# xwoofer.net
KiCad netlist of a schematic drawn in EAGLE
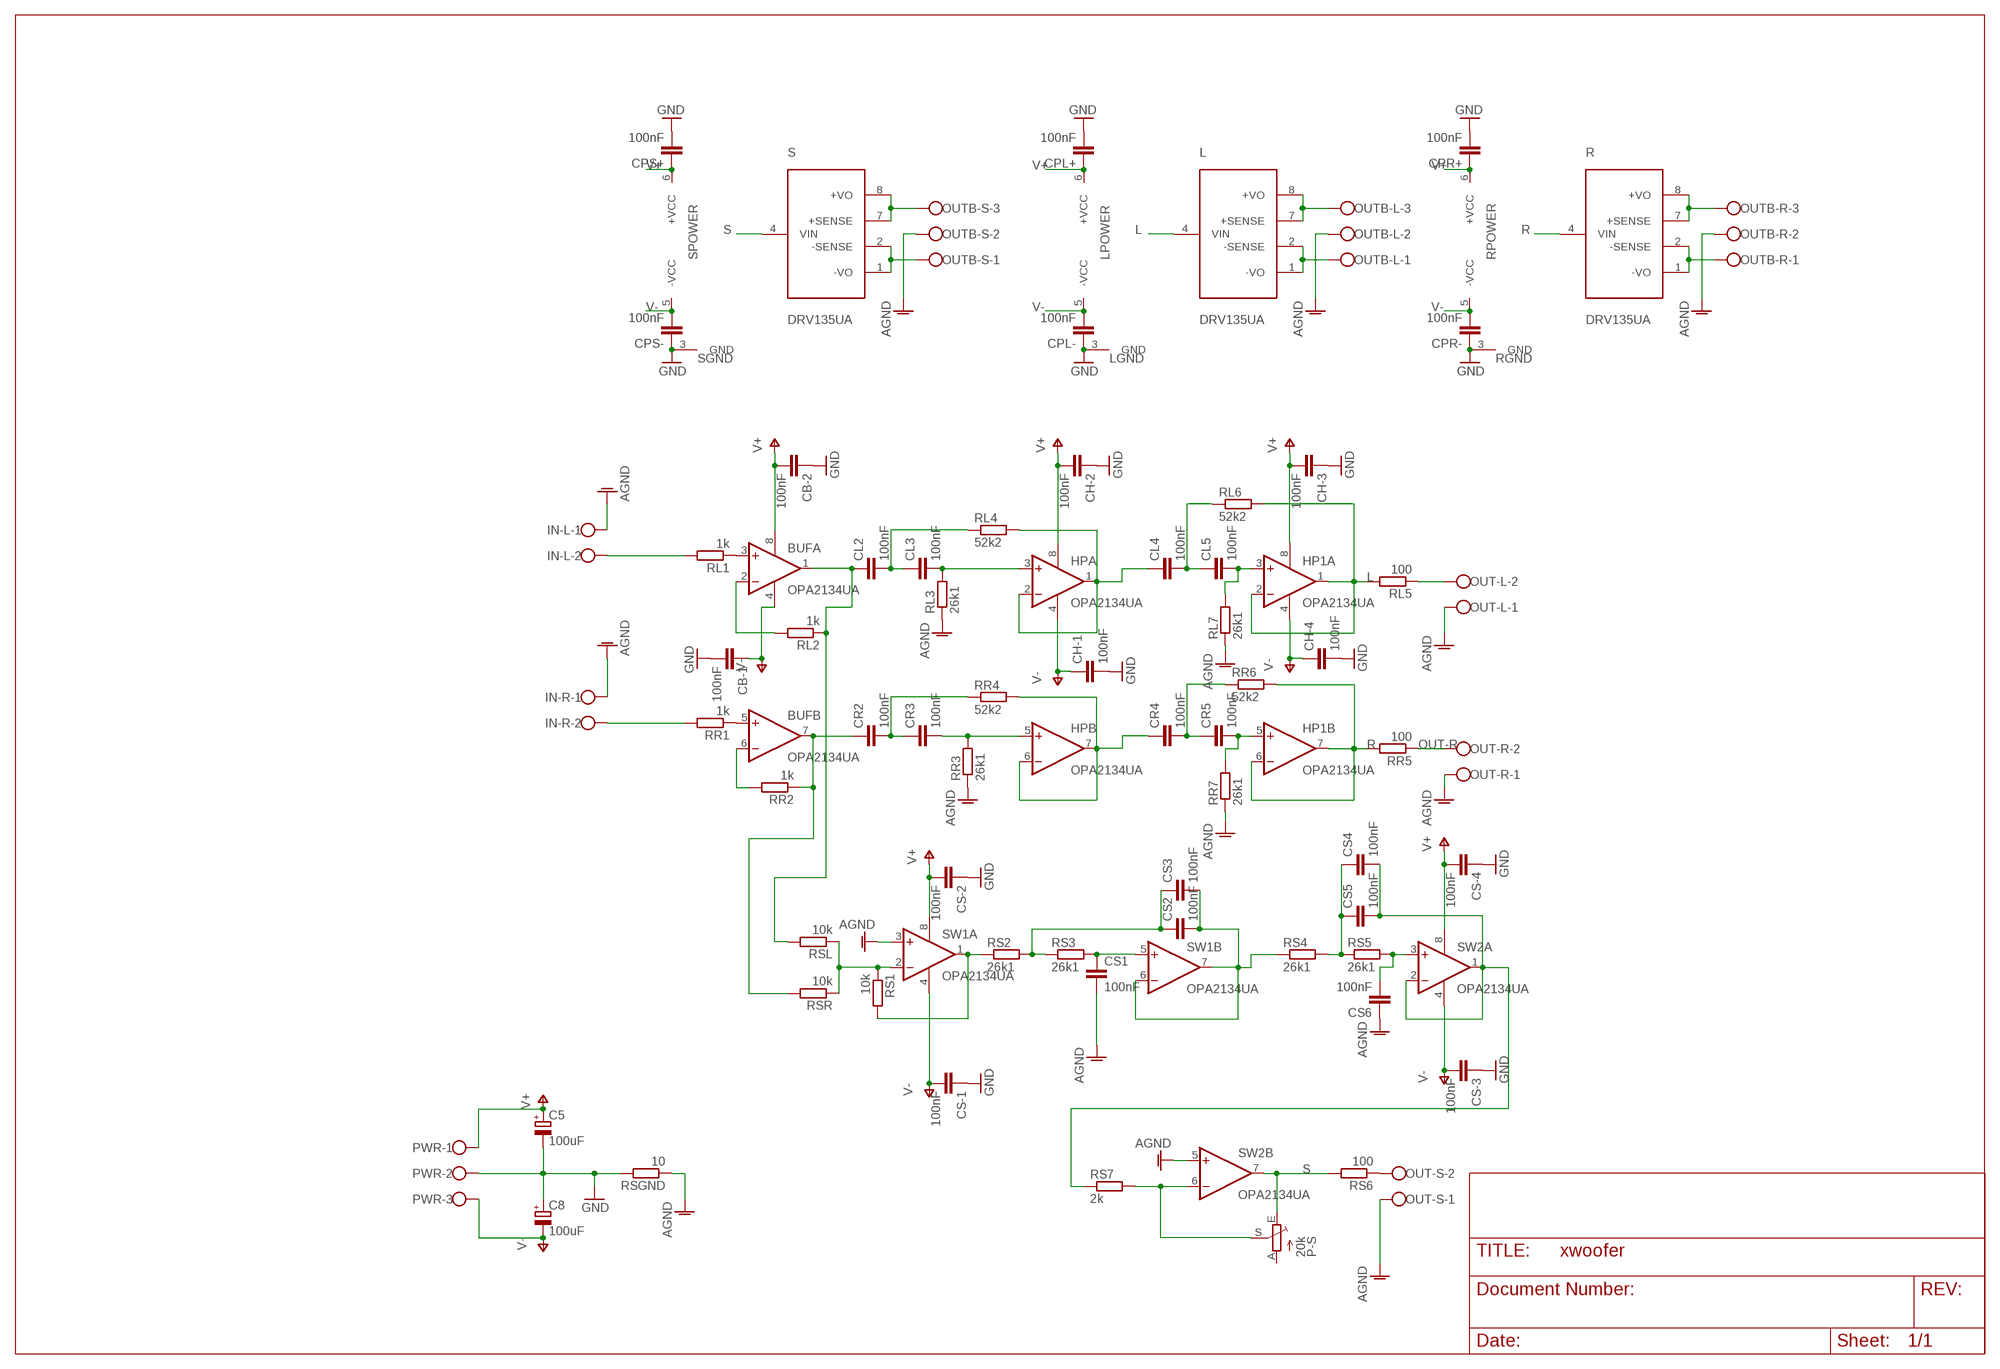
[diagram p0: schematic, sheet 1]

(export (version "E")
  (design (tool "Eeschema 10.0.6"))
  (components
    (comp (ref "BUF")
      (value "OPA2134UA")
      (footprint "eagle-import:SO08")
      (libsource (lib "eagle-import") (part "OPA2UA134"))
    )
    (comp (ref "C5")
      (value "100uF")
      (footprint "eagle-import:E2,5-7")
      (libsource (lib "eagle-import") (part "CPOL-EUE2.5-7"))
    )
    (comp (ref "C8")
      (value "100uF")
      (footprint "eagle-import:E2,5-7")
      (libsource (lib "eagle-import") (part "CPOL-EUE2.5-7"))
    )
    (comp (ref "CB-1")
      (value "100nF")
      (footprint "eagle-import:C0805")
      (libsource (lib "eagle-import") (part "C-EUC0805"))
    )
    (comp (ref "CB-2")
      (value "100nF")
      (footprint "eagle-import:C0805")
      (libsource (lib "eagle-import") (part "C-EUC0805"))
    )
    (comp (ref "CH-1")
      (value "100nF")
      (footprint "eagle-import:C0805K")
      (libsource (lib "eagle-import") (part "C-EUC0805K"))
    )
    (comp (ref "CH-2")
      (value "100nF")
      (footprint "eagle-import:C0805K")
      (libsource (lib "eagle-import") (part "C-EUC0805K"))
    )
    (comp (ref "CH-3")
      (value "100nF")
      (footprint "eagle-import:C0805K")
      (libsource (lib "eagle-import") (part "C-EUC0805K"))
    )
    (comp (ref "CH-4")
      (value "100nF")
      (footprint "eagle-import:C0805K")
      (libsource (lib "eagle-import") (part "C-EUC0805K"))
    )
    (comp (ref "CL2")
      (value "100nF")
      (footprint "eagle-import:C025-025X050")
      (libsource (lib "eagle-import") (part "C-EU025-025X050"))
    )
    (comp (ref "CL3")
      (value "100nF")
      (footprint "eagle-import:C025-025X050")
      (libsource (lib "eagle-import") (part "C-EU025-025X050"))
    )
    (comp (ref "CL4")
      (value "100nF")
      (footprint "eagle-import:C025-025X050")
      (libsource (lib "eagle-import") (part "C-EU025-025X050"))
    )
    (comp (ref "CL5")
      (value "100nF")
      (footprint "eagle-import:C025-025X050")
      (libsource (lib "eagle-import") (part "C-EU025-025X050"))
    )
    (comp (ref "CPL+")
      (value "100nF")
      (footprint "eagle-import:C0805K")
      (libsource (lib "eagle-import") (part "C-EUC0805K"))
    )
    (comp (ref "CPL-")
      (value "100nF")
      (footprint "eagle-import:C0805K")
      (libsource (lib "eagle-import") (part "C-EUC0805K"))
    )
    (comp (ref "CPR+")
      (value "100nF")
      (footprint "eagle-import:C0805K")
      (libsource (lib "eagle-import") (part "C-EUC0805K"))
    )
    (comp (ref "CPR-")
      (value "100nF")
      (footprint "eagle-import:C0805K")
      (libsource (lib "eagle-import") (part "C-EUC0805K"))
    )
    (comp (ref "CPS+")
      (value "100nF")
      (footprint "eagle-import:C0805K")
      (libsource (lib "eagle-import") (part "C-EUC0805K"))
    )
    (comp (ref "CPS-")
      (value "100nF")
      (footprint "eagle-import:C0805K")
      (libsource (lib "eagle-import") (part "C-EUC0805K"))
    )
    (comp (ref "CR2")
      (value "100nF")
      (footprint "eagle-import:C025-025X050")
      (libsource (lib "eagle-import") (part "C-EU025-025X050"))
    )
    (comp (ref "CR3")
      (value "100nF")
      (footprint "eagle-import:C025-025X050")
      (libsource (lib "eagle-import") (part "C-EU025-025X050"))
    )
    (comp (ref "CR4")
      (value "100nF")
      (footprint "eagle-import:C025-025X050")
      (libsource (lib "eagle-import") (part "C-EU025-025X050"))
    )
    (comp (ref "CR5")
      (value "100nF")
      (footprint "eagle-import:C025-025X050")
      (libsource (lib "eagle-import") (part "C-EU025-025X050"))
    )
    (comp (ref "CS-1")
      (value "100nF")
      (footprint "eagle-import:C0805K")
      (libsource (lib "eagle-import") (part "C-EUC0805K"))
    )
    (comp (ref "CS-2")
      (value "100nF")
      (footprint "eagle-import:C0805K")
      (libsource (lib "eagle-import") (part "C-EUC0805K"))
    )
    (comp (ref "CS-3")
      (value "100nF")
      (footprint "eagle-import:C0805K")
      (libsource (lib "eagle-import") (part "C-EUC0805K"))
    )
    (comp (ref "CS-4")
      (value "100nF")
      (footprint "eagle-import:C0805K")
      (libsource (lib "eagle-import") (part "C-EUC0805K"))
    )
    (comp (ref "CS1")
      (value "100nF")
      (footprint "eagle-import:C025-025X050")
      (libsource (lib "eagle-import") (part "C-EU025-025X050"))
    )
    (comp (ref "CS2")
      (value "100nF")
      (footprint "eagle-import:C025-025X050")
      (libsource (lib "eagle-import") (part "C-EU025-025X050"))
    )
    (comp (ref "CS3")
      (value "100nF")
      (footprint "eagle-import:C025-025X050")
      (libsource (lib "eagle-import") (part "C-EU025-025X050"))
    )
    (comp (ref "CS4")
      (value "100nF")
      (footprint "eagle-import:C025-025X050")
      (libsource (lib "eagle-import") (part "C-EU025-025X050"))
    )
    (comp (ref "CS5")
      (value "100nF")
      (footprint "eagle-import:C025-025X050")
      (libsource (lib "eagle-import") (part "C-EU025-025X050"))
    )
    (comp (ref "CS6")
      (value "100nF")
      (footprint "eagle-import:C025-025X050")
      (libsource (lib "eagle-import") (part "C-EU025-025X050"))
    )
    (comp (ref "HP")
      (value "OPA2134UA")
      (footprint "eagle-import:SO08")
      (libsource (lib "eagle-import") (part "OPA2UA134"))
    )
    (comp (ref "HP1")
      (value "OPA2134UA")
      (footprint "eagle-import:SO08")
      (libsource (lib "eagle-import") (part "OPA2UA134"))
    )
    (comp (ref "IN-L")
      (value "W237-102")
      (footprint "eagle-import:W237-102")
      (libsource (lib "eagle-import") (part "W237-102"))
    )
    (comp (ref "IN-R")
      (value "W237-102")
      (footprint "eagle-import:W237-102")
      (libsource (lib "eagle-import") (part "W237-102"))
    )
    (comp (ref "L")
      (value "DRV135UA")
      (footprint "eagle-import:SO08")
      (libsource (lib "eagle-import") (part "DRV135UA"))
    )
    (comp (ref "OUT-L")
      (value "W237-102")
      (footprint "eagle-import:W237-102")
      (libsource (lib "eagle-import") (part "W237-102"))
    )
    (comp (ref "OUT-R")
      (value "W237-102")
      (footprint "eagle-import:W237-102")
      (libsource (lib "eagle-import") (part "W237-102"))
    )
    (comp (ref "OUT-S")
      (value "W237-102")
      (footprint "eagle-import:W237-102")
      (libsource (lib "eagle-import") (part "W237-102"))
    )
    (comp (ref "OUTB-L")
      (value "W237-103")
      (footprint "eagle-import:W237-103")
      (fields (field (name "MPN") "237-103"))
      (libsource (lib "eagle-import") (part "W237-103"))
    )
    (comp (ref "OUTB-R")
      (value "W237-103")
      (footprint "eagle-import:W237-103")
      (fields (field (name "MPN") "237-103"))
      (libsource (lib "eagle-import") (part "W237-103"))
    )
    (comp (ref "OUTB-S")
      (value "W237-103")
      (footprint "eagle-import:W237-103")
      (fields (field (name "MPN") "237-103"))
      (libsource (lib "eagle-import") (part "W237-103"))
    )
    (comp (ref "P-S")
      (value "20k")
      (footprint "eagle-import:B64Y")
      (libsource (lib "eagle-import") (part "TRIM_EU-B64Y"))
    )
    (comp (ref "PWR")
      (value "W237-103")
      (footprint "eagle-import:W237-103")
      (fields (field (name "MPN") "237-103"))
      (libsource (lib "eagle-import") (part "W237-103"))
    )
    (comp (ref "R")
      (value "DRV135UA")
      (footprint "eagle-import:SO08")
      (libsource (lib "eagle-import") (part "DRV135UA"))
    )
    (comp (ref "RL1")
      (value "1k")
      (footprint "eagle-import:R0603")
      (libsource (lib "eagle-import") (part "R-EU_R0603"))
    )
    (comp (ref "RL2")
      (value "1k")
      (footprint "eagle-import:R0603")
      (libsource (lib "eagle-import") (part "R-EU_R0603"))
    )
    (comp (ref "RL3")
      (value "26k1")
      (footprint "eagle-import:R0603")
      (libsource (lib "eagle-import") (part "R-EU_R0603"))
    )
    (comp (ref "RL4")
      (value "52k2")
      (footprint "eagle-import:R0603")
      (libsource (lib "eagle-import") (part "R-EU_R0603"))
    )
    (comp (ref "RL5")
      (value "100")
      (footprint "eagle-import:R1206")
      (libsource (lib "eagle-import") (part "R-EU_R1206"))
    )
    (comp (ref "RL6")
      (value "52k2")
      (footprint "eagle-import:R0603")
      (libsource (lib "eagle-import") (part "R-EU_R0603"))
    )
    (comp (ref "RL7")
      (value "26k1")
      (footprint "eagle-import:R0603")
      (libsource (lib "eagle-import") (part "R-EU_R0603"))
    )
    (comp (ref "RR1")
      (value "1k")
      (footprint "eagle-import:R0603")
      (libsource (lib "eagle-import") (part "R-EU_R0603"))
    )
    (comp (ref "RR2")
      (value "1k")
      (footprint "eagle-import:R0603")
      (libsource (lib "eagle-import") (part "R-EU_R0603"))
    )
    (comp (ref "RR3")
      (value "26k1")
      (footprint "eagle-import:R0603")
      (libsource (lib "eagle-import") (part "R-EU_R0603"))
    )
    (comp (ref "RR4")
      (value "52k2")
      (footprint "eagle-import:R0603")
      (libsource (lib "eagle-import") (part "R-EU_R0603"))
    )
    (comp (ref "RR5")
      (value "100")
      (footprint "eagle-import:R1206")
      (libsource (lib "eagle-import") (part "R-EU_R1206"))
    )
    (comp (ref "RR6")
      (value "52k2")
      (footprint "eagle-import:R0603")
      (libsource (lib "eagle-import") (part "R-EU_R0603"))
    )
    (comp (ref "RR7")
      (value "26k1")
      (footprint "eagle-import:R0603")
      (libsource (lib "eagle-import") (part "R-EU_R0603"))
    )
    (comp (ref "RS1")
      (value "10k")
      (footprint "eagle-import:R0603")
      (libsource (lib "eagle-import") (part "R-EU_R0603"))
    )
    (comp (ref "RS2")
      (value "26k1")
      (footprint "eagle-import:R0603")
      (libsource (lib "eagle-import") (part "R-EU_R0603"))
    )
    (comp (ref "RS3")
      (value "26k1")
      (footprint "eagle-import:R0603")
      (libsource (lib "eagle-import") (part "R-EU_R0603"))
    )
    (comp (ref "RS4")
      (value "26k1")
      (footprint "eagle-import:R0603")
      (libsource (lib "eagle-import") (part "R-EU_R0603"))
    )
    (comp (ref "RS5")
      (value "26k1")
      (footprint "eagle-import:R0603")
      (libsource (lib "eagle-import") (part "R-EU_R0603"))
    )
    (comp (ref "RS6")
      (value "100")
      (footprint "eagle-import:R1206")
      (libsource (lib "eagle-import") (part "R-EU_R1206"))
    )
    (comp (ref "RS7")
      (value "2k")
      (footprint "eagle-import:R0603")
      (libsource (lib "eagle-import") (part "R-EU_R0603"))
    )
    (comp (ref "RSGND")
      (value "10")
      (footprint "eagle-import:R1206")
      (libsource (lib "eagle-import") (part "R-EU_R1206"))
    )
    (comp (ref "RSL")
      (value "10k")
      (footprint "eagle-import:R0603")
      (libsource (lib "eagle-import") (part "R-EU_R0603"))
    )
    (comp (ref "RSR")
      (value "10k")
      (footprint "eagle-import:R0603")
      (libsource (lib "eagle-import") (part "R-EU_R0603"))
    )
    (comp (ref "S")
      (value "DRV135UA")
      (footprint "eagle-import:SO08")
      (libsource (lib "eagle-import") (part "DRV135UA"))
    )
    (comp (ref "SW1")
      (value "OPA2134UA")
      (footprint "eagle-import:SO08")
      (libsource (lib "eagle-import") (part "OPA2UA134"))
    )
    (comp (ref "SW2")
      (value "OPA2134UA")
      (footprint "eagle-import:SO08")
      (libsource (lib "eagle-import") (part "OPA2UA134"))
    )
  )
  (nets
    (net (code "1") (name "/L") (class "Default")
      (node (ref "HP1") (pin "1") (pinfunction "OUT_1") (pintype "output"))
      (node (ref "HP1") (pin "2") (pinfunction "-IN_2") (pintype "input"))
      (node (ref "L") (pin "4") (pinfunction "VIN_4") (pintype "bidirectional"))
      (node (ref "RL5") (pin "2") (pinfunction "2_2") (pintype "passive"))
      (node (ref "RL6") (pin "2") (pinfunction "2_2") (pintype "passive"))
    )
    (net (code "2") (name "/OUT-R") (class "Default")
      (node (ref "OUT-R") (pin "2") (pinfunction "KL_2") (pintype "passive"))
      (node (ref "RR5") (pin "1") (pinfunction "1_1") (pintype "passive"))
    )
    (net (code "3") (name "/R") (class "Default")
      (node (ref "HP1") (pin "6") (pinfunction "-IN_6") (pintype "input"))
      (node (ref "HP1") (pin "7") (pinfunction "OUT_7") (pintype "output"))
      (node (ref "R") (pin "4") (pinfunction "VIN_4") (pintype "bidirectional"))
      (node (ref "RR5") (pin "2") (pinfunction "2_2") (pintype "passive"))
      (node (ref "RR6") (pin "2") (pinfunction "2_2") (pintype "passive"))
    )
    (net (code "4") (name "/S") (class "Default")
      (node (ref "P-S") (pin "E") (pinfunction "E_E") (pintype "passive"))
      (node (ref "RS6") (pin "2") (pinfunction "2_2") (pintype "passive"))
      (node (ref "S") (pin "4") (pinfunction "VIN_4") (pintype "bidirectional"))
      (node (ref "SW2") (pin "7") (pinfunction "OUT_7") (pintype "output"))
    )
    (net (code "5") (name "AGND") (class "Default")
      (node (ref "CS1") (pin "2") (pinfunction "2_2") (pintype "passive"))
      (node (ref "CS6") (pin "1") (pinfunction "1_1") (pintype "passive"))
      (node (ref "IN-L") (pin "1") (pinfunction "KL_1") (pintype "passive"))
      (node (ref "IN-R") (pin "1") (pinfunction "KL_1") (pintype "passive"))
      (node (ref "OUT-L") (pin "1") (pinfunction "KL_1") (pintype "passive"))
      (node (ref "OUT-R") (pin "1") (pinfunction "KL_1") (pintype "passive"))
      (node (ref "OUT-S") (pin "1") (pinfunction "KL_1") (pintype "passive"))
      (node (ref "OUTB-L") (pin "2") (pinfunction "KL_2") (pintype "passive"))
      (node (ref "OUTB-R") (pin "2") (pinfunction "KL_2") (pintype "passive"))
      (node (ref "OUTB-S") (pin "2") (pinfunction "KL_2") (pintype "passive"))
      (node (ref "RL3") (pin "1") (pinfunction "1_1") (pintype "passive"))
      (node (ref "RL7") (pin "1") (pinfunction "1_1") (pintype "passive"))
      (node (ref "RR3") (pin "1") (pinfunction "1_1") (pintype "passive"))
      (node (ref "RR7") (pin "1") (pinfunction "1_1") (pintype "passive"))
      (node (ref "RSGND") (pin "1") (pinfunction "1_1") (pintype "passive"))
      (node (ref "SW1") (pin "3") (pinfunction "+IN_3") (pintype "input"))
      (node (ref "SW2") (pin "5") (pinfunction "+IN_5") (pintype "input"))
    )
    (net (code "6") (name "GND") (class "Default")
      (node (ref "C5") (pin "-") (pinfunction "-_-") (pintype "passive"))
      (node (ref "C8") (pin "+") (pinfunction "+_+") (pintype "passive"))
      (node (ref "CB-1") (pin "2") (pinfunction "2_2") (pintype "passive"))
      (node (ref "CB-2") (pin "1") (pinfunction "1_1") (pintype "passive"))
      (node (ref "CH-1") (pin "2") (pinfunction "2_2") (pintype "passive"))
      (node (ref "CH-2") (pin "1") (pinfunction "1_1") (pintype "passive"))
      (node (ref "CH-3") (pin "1") (pinfunction "1_1") (pintype "passive"))
      (node (ref "CH-4") (pin "2") (pinfunction "2_2") (pintype "passive"))
      (node (ref "CPL+") (pin "2") (pinfunction "2_2") (pintype "passive"))
      (node (ref "CPL-") (pin "1") (pinfunction "1_1") (pintype "passive"))
      (node (ref "CPR+") (pin "2") (pinfunction "2_2") (pintype "passive"))
      (node (ref "CPR-") (pin "1") (pinfunction "1_1") (pintype "passive"))
      (node (ref "CPS+") (pin "2") (pinfunction "2_2") (pintype "passive"))
      (node (ref "CPS-") (pin "1") (pinfunction "1_1") (pintype "passive"))
      (node (ref "CS-1") (pin "1") (pinfunction "1_1") (pintype "passive"))
      (node (ref "CS-2") (pin "1") (pinfunction "1_1") (pintype "passive"))
      (node (ref "CS-3") (pin "1") (pinfunction "1_1") (pintype "passive"))
      (node (ref "CS-4") (pin "1") (pinfunction "1_1") (pintype "passive"))
      (node (ref "L") (pin "3") (pinfunction "GND_3") (pintype "power_in"))
      (node (ref "PWR") (pin "2") (pinfunction "KL_2") (pintype "passive"))
      (node (ref "R") (pin "3") (pinfunction "GND_3") (pintype "power_in"))
      (node (ref "RSGND") (pin "2") (pinfunction "2_2") (pintype "passive"))
      (node (ref "S") (pin "3") (pinfunction "GND_3") (pintype "power_in"))
    )
    (net (code "7") (name "Net-(BUFA-+IN)") (class "Default")
      (node (ref "BUF") (pin "3") (pinfunction "+IN_3") (pintype "input"))
      (node (ref "RL1") (pin "1") (pinfunction "1_1") (pintype "passive"))
    )
    (net (code "8") (name "Net-(BUFA--IN)") (class "Default")
      (node (ref "BUF") (pin "2") (pinfunction "-IN_2") (pintype "input"))
      (node (ref "RL2") (pin "2") (pinfunction "2_2") (pintype "passive"))
    )
    (net (code "9") (name "Net-(BUFA-OUT)") (class "Default")
      (node (ref "BUF") (pin "1") (pinfunction "OUT_1") (pintype "output"))
      (node (ref "CL2") (pin "1") (pinfunction "1_1") (pintype "passive"))
      (node (ref "RL2") (pin "1") (pinfunction "1_1") (pintype "passive"))
      (node (ref "RSL") (pin "2") (pinfunction "2_2") (pintype "passive"))
    )
    (net (code "10") (name "Net-(BUFB-+IN)") (class "Default")
      (node (ref "BUF") (pin "5") (pinfunction "+IN_5") (pintype "input"))
      (node (ref "RR1") (pin "1") (pinfunction "1_1") (pintype "passive"))
    )
    (net (code "11") (name "Net-(BUFB--IN)") (class "Default")
      (node (ref "BUF") (pin "6") (pinfunction "-IN_6") (pintype "input"))
      (node (ref "RR2") (pin "2") (pinfunction "2_2") (pintype "passive"))
    )
    (net (code "12") (name "Net-(BUFB-OUT)") (class "Default")
      (node (ref "BUF") (pin "7") (pinfunction "OUT_7") (pintype "output"))
      (node (ref "CR2") (pin "1") (pinfunction "1_1") (pintype "passive"))
      (node (ref "RR2") (pin "1") (pinfunction "1_1") (pintype "passive"))
      (node (ref "RSR") (pin "2") (pinfunction "2_2") (pintype "passive"))
    )
    (net (code "13") (name "Net-(CL2-Pad2)") (class "Default")
      (node (ref "CL2") (pin "2") (pinfunction "2_2") (pintype "passive"))
      (node (ref "CL3") (pin "1") (pinfunction "1_1") (pintype "passive"))
      (node (ref "RL4") (pin "1") (pinfunction "1_1") (pintype "passive"))
    )
    (net (code "14") (name "Net-(CL4-Pad2)") (class "Default")
      (node (ref "CL4") (pin "2") (pinfunction "2_2") (pintype "passive"))
      (node (ref "CL5") (pin "1") (pinfunction "1_1") (pintype "passive"))
      (node (ref "RL6") (pin "1") (pinfunction "1_1") (pintype "passive"))
    )
    (net (code "15") (name "Net-(CR2-Pad2)") (class "Default")
      (node (ref "CR2") (pin "2") (pinfunction "2_2") (pintype "passive"))
      (node (ref "CR3") (pin "1") (pinfunction "1_1") (pintype "passive"))
      (node (ref "RR4") (pin "1") (pinfunction "1_1") (pintype "passive"))
    )
    (net (code "16") (name "Net-(CR4-Pad2)") (class "Default")
      (node (ref "CR4") (pin "2") (pinfunction "2_2") (pintype "passive"))
      (node (ref "CR5") (pin "1") (pinfunction "1_1") (pintype "passive"))
      (node (ref "RR6") (pin "1") (pinfunction "1_1") (pintype "passive"))
    )
    (net (code "17") (name "Net-(CS2-Pad1)") (class "Default")
      (node (ref "CS2") (pin "1") (pinfunction "1_1") (pintype "passive"))
      (node (ref "CS3") (pin "1") (pinfunction "1_1") (pintype "passive"))
      (node (ref "RS2") (pin "2") (pinfunction "2_2") (pintype "passive"))
      (node (ref "RS3") (pin "1") (pinfunction "1_1") (pintype "passive"))
    )
    (net (code "18") (name "Net-(CS4-Pad1)") (class "Default")
      (node (ref "CS4") (pin "1") (pinfunction "1_1") (pintype "passive"))
      (node (ref "CS5") (pin "1") (pinfunction "1_1") (pintype "passive"))
      (node (ref "RS4") (pin "2") (pinfunction "2_2") (pintype "passive"))
      (node (ref "RS5") (pin "1") (pinfunction "1_1") (pintype "passive"))
    )
    (net (code "19") (name "Net-(HP1A-+IN)") (class "Default")
      (node (ref "CL5") (pin "2") (pinfunction "2_2") (pintype "passive"))
      (node (ref "HP1") (pin "3") (pinfunction "+IN_3") (pintype "input"))
      (node (ref "RL7") (pin "2") (pinfunction "2_2") (pintype "passive"))
    )
    (net (code "20") (name "Net-(HP1B-+IN)") (class "Default")
      (node (ref "CR5") (pin "2") (pinfunction "2_2") (pintype "passive"))
      (node (ref "HP1") (pin "5") (pinfunction "+IN_5") (pintype "input"))
      (node (ref "RR7") (pin "2") (pinfunction "2_2") (pintype "passive"))
    )
    (net (code "21") (name "Net-(HPA-+IN)") (class "Default")
      (node (ref "CL3") (pin "2") (pinfunction "2_2") (pintype "passive"))
      (node (ref "HP") (pin "3") (pinfunction "+IN_3") (pintype "input"))
      (node (ref "RL3") (pin "2") (pinfunction "2_2") (pintype "passive"))
    )
    (net (code "22") (name "Net-(HPA--IN)") (class "Default")
      (node (ref "CL4") (pin "1") (pinfunction "1_1") (pintype "passive"))
      (node (ref "HP") (pin "1") (pinfunction "OUT_1") (pintype "output"))
      (node (ref "HP") (pin "2") (pinfunction "-IN_2") (pintype "input"))
      (node (ref "RL4") (pin "2") (pinfunction "2_2") (pintype "passive"))
    )
    (net (code "23") (name "Net-(HPB-+IN)") (class "Default")
      (node (ref "CR3") (pin "2") (pinfunction "2_2") (pintype "passive"))
      (node (ref "HP") (pin "5") (pinfunction "+IN_5") (pintype "input"))
      (node (ref "RR3") (pin "2") (pinfunction "2_2") (pintype "passive"))
    )
    (net (code "24") (name "Net-(HPB--IN)") (class "Default")
      (node (ref "CR4") (pin "1") (pinfunction "1_1") (pintype "passive"))
      (node (ref "HP") (pin "6") (pinfunction "-IN_6") (pintype "input"))
      (node (ref "HP") (pin "7") (pinfunction "OUT_7") (pintype "output"))
      (node (ref "RR4") (pin "2") (pinfunction "2_2") (pintype "passive"))
    )
    (net (code "25") (name "Net-(IN-LB-KL)") (class "Default")
      (node (ref "IN-L") (pin "2") (pinfunction "KL_2") (pintype "passive"))
      (node (ref "RL1") (pin "2") (pinfunction "2_2") (pintype "passive"))
    )
    (net (code "26") (name "Net-(IN-RB-KL)") (class "Default")
      (node (ref "IN-R") (pin "2") (pinfunction "KL_2") (pintype "passive"))
      (node (ref "RR1") (pin "2") (pinfunction "2_2") (pintype "passive"))
    )
    (net (code "27") (name "Net-(LA-+SENSE)") (class "Default")
      (node (ref "L") (pin "7") (pinfunction "+SENSE_7") (pintype "bidirectional"))
      (node (ref "L") (pin "8") (pinfunction "+VO_8") (pintype "bidirectional"))
      (node (ref "OUTB-L") (pin "3") (pinfunction "KL_3") (pintype "passive"))
    )
    (net (code "28") (name "Net-(LA--SENSE)") (class "Default")
      (node (ref "L") (pin "1") (pinfunction "-VO_1") (pintype "bidirectional"))
      (node (ref "L") (pin "2") (pinfunction "-SENSE_2") (pintype "bidirectional"))
      (node (ref "OUTB-L") (pin "1") (pinfunction "KL_1") (pintype "passive"))
    )
    (net (code "29") (name "Net-(OUT-LB-KL)") (class "Default")
      (node (ref "OUT-L") (pin "2") (pinfunction "KL_2") (pintype "passive"))
      (node (ref "RL5") (pin "1") (pinfunction "1_1") (pintype "passive"))
    )
    (net (code "30") (name "Net-(OUT-SB-KL)") (class "Default")
      (node (ref "OUT-S") (pin "2") (pinfunction "KL_2") (pintype "passive"))
      (node (ref "RS6") (pin "1") (pinfunction "1_1") (pintype "passive"))
    )
    (net (code "31") (name "Net-(OUTB-RA-KL)") (class "Default")
      (node (ref "OUTB-R") (pin "1") (pinfunction "KL_1") (pintype "passive"))
      (node (ref "R") (pin "1") (pinfunction "-VO_1") (pintype "bidirectional"))
      (node (ref "R") (pin "2") (pinfunction "-SENSE_2") (pintype "bidirectional"))
    )
    (net (code "32") (name "Net-(OUTB-RC-KL)") (class "Default")
      (node (ref "OUTB-R") (pin "3") (pinfunction "KL_3") (pintype "passive"))
      (node (ref "R") (pin "7") (pinfunction "+SENSE_7") (pintype "bidirectional"))
      (node (ref "R") (pin "8") (pinfunction "+VO_8") (pintype "bidirectional"))
    )
    (net (code "33") (name "Net-(OUTB-SA-KL)") (class "Default")
      (node (ref "OUTB-S") (pin "1") (pinfunction "KL_1") (pintype "passive"))
      (node (ref "S") (pin "1") (pinfunction "-VO_1") (pintype "bidirectional"))
      (node (ref "S") (pin "2") (pinfunction "-SENSE_2") (pintype "bidirectional"))
    )
    (net (code "34") (name "Net-(OUTB-SC-KL)") (class "Default")
      (node (ref "OUTB-S") (pin "3") (pinfunction "KL_3") (pintype "passive"))
      (node (ref "S") (pin "7") (pinfunction "+SENSE_7") (pintype "bidirectional"))
      (node (ref "S") (pin "8") (pinfunction "+VO_8") (pintype "bidirectional"))
    )
    (net (code "35") (name "Net-(SW1A--IN)") (class "Default")
      (node (ref "RS1") (pin "1") (pinfunction "1_1") (pintype "passive"))
      (node (ref "RSL") (pin "1") (pinfunction "1_1") (pintype "passive"))
      (node (ref "RSR") (pin "1") (pinfunction "1_1") (pintype "passive"))
      (node (ref "SW1") (pin "2") (pinfunction "-IN_2") (pintype "input"))
    )
    (net (code "36") (name "Net-(SW1A-OUT)") (class "Default")
      (node (ref "RS1") (pin "2") (pinfunction "2_2") (pintype "passive"))
      (node (ref "RS2") (pin "1") (pinfunction "1_1") (pintype "passive"))
      (node (ref "SW1") (pin "1") (pinfunction "OUT_1") (pintype "output"))
    )
    (net (code "37") (name "Net-(SW1B-+IN)") (class "Default")
      (node (ref "CS1") (pin "1") (pinfunction "1_1") (pintype "passive"))
      (node (ref "RS3") (pin "2") (pinfunction "2_2") (pintype "passive"))
      (node (ref "SW1") (pin "5") (pinfunction "+IN_5") (pintype "input"))
    )
    (net (code "38") (name "Net-(SW1B--IN)") (class "Default")
      (node (ref "CS2") (pin "2") (pinfunction "2_2") (pintype "passive"))
      (node (ref "CS3") (pin "2") (pinfunction "2_2") (pintype "passive"))
      (node (ref "RS4") (pin "1") (pinfunction "1_1") (pintype "passive"))
      (node (ref "SW1") (pin "6") (pinfunction "-IN_6") (pintype "input"))
      (node (ref "SW1") (pin "7") (pinfunction "OUT_7") (pintype "output"))
    )
    (net (code "39") (name "Net-(SW2A-+IN)") (class "Default")
      (node (ref "CS6") (pin "2") (pinfunction "2_2") (pintype "passive"))
      (node (ref "RS5") (pin "2") (pinfunction "2_2") (pintype "passive"))
      (node (ref "SW2") (pin "3") (pinfunction "+IN_3") (pintype "input"))
    )
    (net (code "40") (name "Net-(SW2A--IN)") (class "Default")
      (node (ref "CS4") (pin "2") (pinfunction "2_2") (pintype "passive"))
      (node (ref "CS5") (pin "2") (pinfunction "2_2") (pintype "passive"))
      (node (ref "RS7") (pin "1") (pinfunction "1_1") (pintype "passive"))
      (node (ref "SW2") (pin "1") (pinfunction "OUT_1") (pintype "output"))
      (node (ref "SW2") (pin "2") (pinfunction "-IN_2") (pintype "input"))
    )
    (net (code "41") (name "Net-(SW2B--IN)") (class "Default")
      (node (ref "P-S") (pin "S") (pinfunction "S_S") (pintype "passive"))
      (node (ref "RS7") (pin "2") (pinfunction "2_2") (pintype "passive"))
      (node (ref "SW2") (pin "6") (pinfunction "-IN_6") (pintype "input"))
    )
    (net (code "42") (name "V+") (class "Default")
      (node (ref "BUF") (pin "8") (pinfunction "V+_8") (pintype "power_in"))
      (node (ref "C5") (pin "+") (pinfunction "+_+") (pintype "passive"))
      (node (ref "CB-2") (pin "2") (pinfunction "2_2") (pintype "passive"))
      (node (ref "CH-2") (pin "2") (pinfunction "2_2") (pintype "passive"))
      (node (ref "CH-3") (pin "2") (pinfunction "2_2") (pintype "passive"))
      (node (ref "CPL+") (pin "1") (pinfunction "1_1") (pintype "passive"))
      (node (ref "CPR+") (pin "1") (pinfunction "1_1") (pintype "passive"))
      (node (ref "CPS+") (pin "1") (pinfunction "1_1") (pintype "passive"))
      (node (ref "CS-2") (pin "2") (pinfunction "2_2") (pintype "passive"))
      (node (ref "CS-4") (pin "2") (pinfunction "2_2") (pintype "passive"))
      (node (ref "HP") (pin "8") (pinfunction "V+_8") (pintype "power_in"))
      (node (ref "HP1") (pin "8") (pinfunction "V+_8") (pintype "power_in"))
      (node (ref "L") (pin "6") (pinfunction "+VCC_6") (pintype "power_in"))
      (node (ref "PWR") (pin "1") (pinfunction "KL_1") (pintype "passive"))
      (node (ref "R") (pin "6") (pinfunction "+VCC_6") (pintype "power_in"))
      (node (ref "S") (pin "6") (pinfunction "+VCC_6") (pintype "power_in"))
      (node (ref "SW1") (pin "8") (pinfunction "V+_8") (pintype "power_in"))
      (node (ref "SW2") (pin "8") (pinfunction "V+_8") (pintype "power_in"))
    )
    (net (code "43") (name "V-") (class "Default")
      (node (ref "BUF") (pin "4") (pinfunction "V-_4") (pintype "power_in"))
      (node (ref "C8") (pin "-") (pinfunction "-_-") (pintype "passive"))
      (node (ref "CB-1") (pin "1") (pinfunction "1_1") (pintype "passive"))
      (node (ref "CH-1") (pin "1") (pinfunction "1_1") (pintype "passive"))
      (node (ref "CH-4") (pin "1") (pinfunction "1_1") (pintype "passive"))
      (node (ref "CPL-") (pin "2") (pinfunction "2_2") (pintype "passive"))
      (node (ref "CPR-") (pin "2") (pinfunction "2_2") (pintype "passive"))
      (node (ref "CPS-") (pin "2") (pinfunction "2_2") (pintype "passive"))
      (node (ref "CS-1") (pin "2") (pinfunction "2_2") (pintype "passive"))
      (node (ref "CS-3") (pin "2") (pinfunction "2_2") (pintype "passive"))
      (node (ref "HP") (pin "4") (pinfunction "V-_4") (pintype "power_in"))
      (node (ref "HP1") (pin "4") (pinfunction "V-_4") (pintype "power_in"))
      (node (ref "L") (pin "5") (pinfunction "-VCC_5") (pintype "power_in"))
      (node (ref "PWR") (pin "3") (pinfunction "KL_3") (pintype "passive"))
      (node (ref "R") (pin "5") (pinfunction "-VCC_5") (pintype "power_in"))
      (node (ref "S") (pin "5") (pinfunction "-VCC_5") (pintype "power_in"))
      (node (ref "SW1") (pin "4") (pinfunction "V-_4") (pintype "power_in"))
      (node (ref "SW2") (pin "4") (pinfunction "V-_4") (pintype "power_in"))
    )
    (net (code "44") (name "unconnected-(P-S-PadA)") (class "Default")
      (node (ref "P-S") (pin "A") (pinfunction "A_A") (pintype "passive"))
    )
  )
)
